# SCH___2022-06-13.net
KiCad netlist of a schematic drawn in EasyEDA
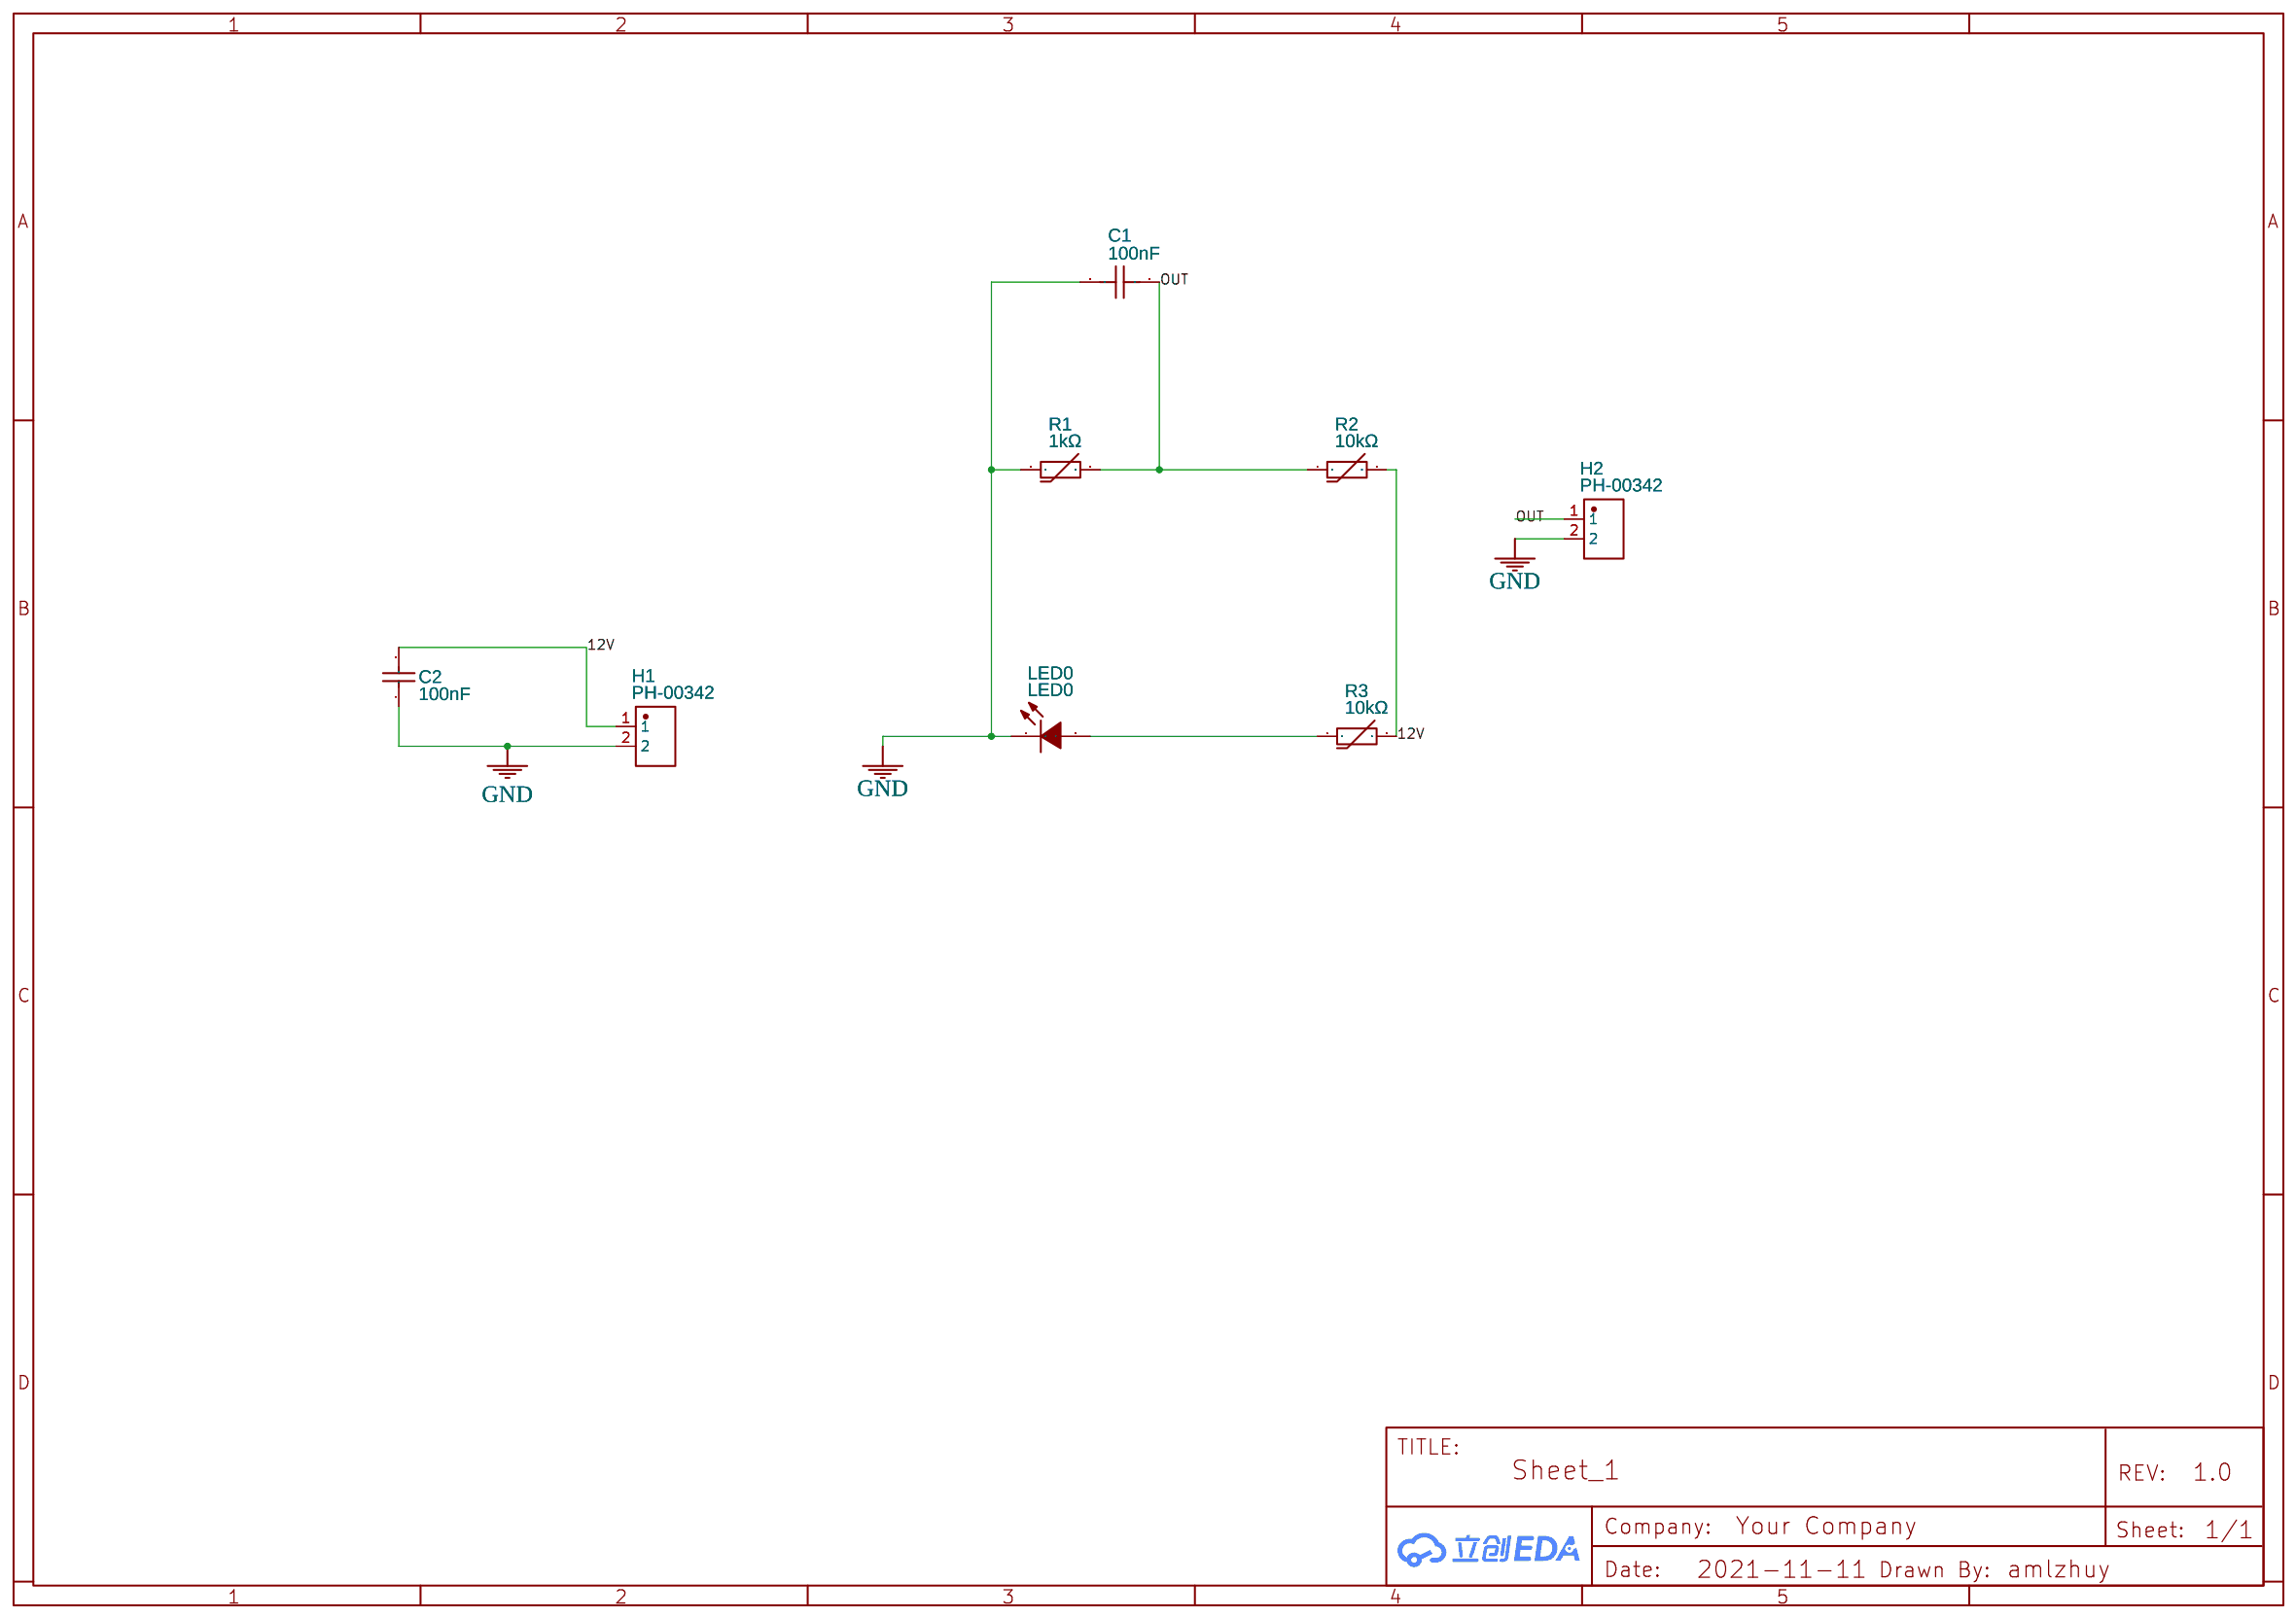
[diagram p0: schematic sheet]

(export (version "E")
  (design (tool "Eeschema 10.0.6"))
  (components
    (comp (ref "C1")
      (value "100nF")
      (fields
        (field (name "BOM_Manufacturer Part") "CL10B104KB8NNNC")
        (field (name "BOM_Supplier Part") "C1591")
      )
      (libsource (lib "") (part "CL10B104KB8NNNC"))
    )
    (comp (ref "C2")
      (value "100nF")
      (fields
        (field (name "BOM_Manufacturer Part") "CL10B104JB8NNNC")
        (field (name "BOM_Supplier Part") "C24452")
      )
      (libsource (lib "") (part "CL10B104JB8NNNC"))
    )
    (comp (ref "H1")
      (value "PH-00342")
      (fields (field (name "BOM_Supplier Part") "C2685154"))
      (libsource (lib "") (part "PH-00342"))
    )
    (comp (ref "H2")
      (value "PH-00342")
      (fields (field (name "BOM_Supplier Part") "C2685154"))
      (libsource (lib "") (part "PH-00342"))
    )
    (comp (ref "LED0")
      (value "LED0")
      (fields
        (field (name "BOM_Manufacturer Part") "FC-1608UGK-520D")
        (field (name "BOM_Supplier Part") "C87326")
      )
      (libsource (lib "") (part "FC-1608UGK-520D"))
    )
    (comp (ref "R1")
      (value "1kΩ")
      (fields
        (field (name "BOM_Manufacturer Part") "SDNT1608X103J3450HTF")
        (field (name "BOM_Supplier Part") "C43113")
      )
      (libsource (lib "") (part "SDNT1608X103J3450HTF"))
    )
    (comp (ref "R2")
      (value "10kΩ")
      (fields
        (field (name "BOM_Manufacturer Part") "SDNT1608X103J3450HTF")
        (field (name "BOM_Supplier Part") "C43113")
      )
      (libsource (lib "") (part "SDNT1608X103J3450HTF"))
    )
    (comp (ref "R3")
      (value "10kΩ")
      (fields
        (field (name "BOM_Manufacturer Part") "SDNT1608X103J3450HTF")
        (field (name "BOM_Supplier Part") "C43113")
      )
      (libsource (lib "") (part "SDNT1608X103J3450HTF"))
    )
  )
  (nets
    (net (code "1") (name "/12V") (class "Default")
      (node (ref "C2") (pin "2") (pinfunction "2_2") (pintype "input"))
      (node (ref "H1") (pin "1") (pinfunction "1_1") (pintype "unspecified"))
      (node (ref "R2") (pin "2") (pinfunction "2_2") (pintype "input"))
      (node (ref "R3") (pin "2") (pinfunction "2_2") (pintype "input"))
    )
    (net (code "2") (name "/OUT") (class "Default")
      (node (ref "C1") (pin "2") (pinfunction "2_2") (pintype "unspecified"))
      (node (ref "H2") (pin "1") (pinfunction "1_1") (pintype "unspecified"))
      (node (ref "R1") (pin "2") (pinfunction "2_2") (pintype "input"))
      (node (ref "R2") (pin "1") (pinfunction "1_1") (pintype "input"))
    )
    (net (code "3") (name "GND") (class "Default")
      (node (ref "C1") (pin "1") (pinfunction "1_1") (pintype "unspecified"))
      (node (ref "C2") (pin "1") (pinfunction "1_1") (pintype "input"))
      (node (ref "H1") (pin "2") (pinfunction "2_2") (pintype "unspecified"))
      (node (ref "H2") (pin "2") (pinfunction "2_2") (pintype "unspecified"))
      (node (ref "LED0") (pin "1") (pinfunction "K_1") (pintype "unspecified"))
      (node (ref "R1") (pin "1") (pinfunction "1_1") (pintype "input"))
    )
    (net (code "4") (name "Net-(LED0-A)") (class "Default")
      (node (ref "LED0") (pin "2") (pinfunction "A_2") (pintype "unspecified"))
      (node (ref "R3") (pin "1") (pinfunction "1_1") (pintype "input"))
    )
  )
)
